# tester.net
KiCad netlist of a schematic drawn in EAGLE
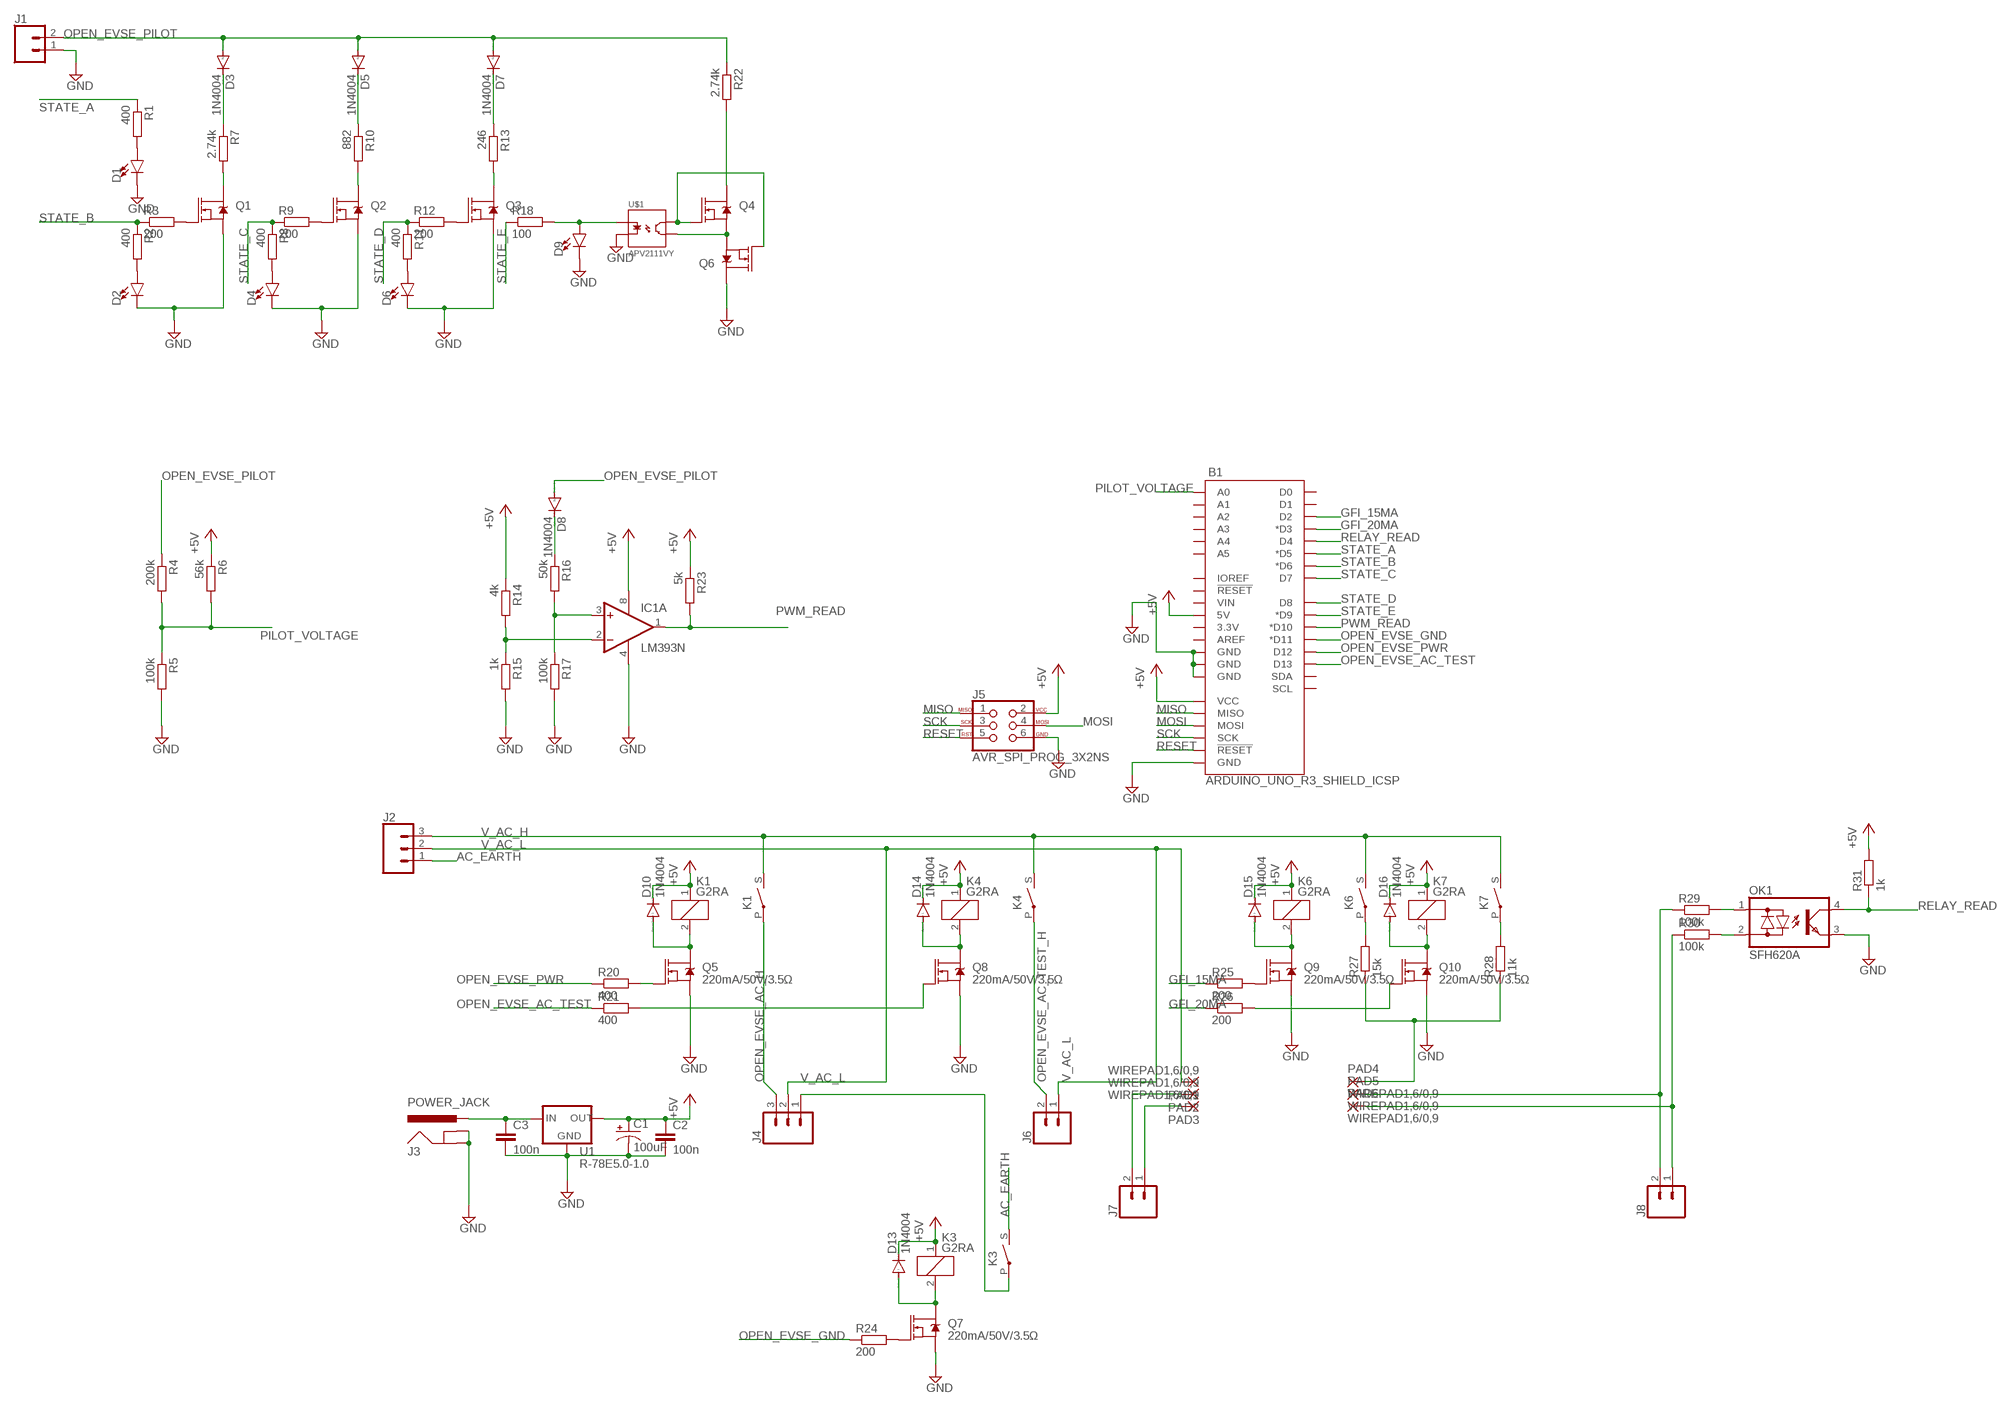
[diagram p0: schematic, sheet 1]

(export (version "E")
  (design (tool "Eeschema 10.0.6"))
  (components
    (comp (ref "B1")
      (value "ARDUINO_UNO_R3_SHIELD_ICSP")
      (footprint "eagle-import:UNO_R3_SHIELD_ICSP")
      (libsource (lib "eagle-import") (part "ARDUINO_UNO_R3_SHIELD_ICSP"))
    )
    (comp (ref "C1")
      (value "100uF")
      (footprint "eagle-import:CPOL-RADIAL-2.5MM-6.5MM")
      (libsource (lib "eagle-import") (part "100UF-POLAR-RADIAL-2.5MM-25V-20%"))
    )
    (comp (ref "C2")
      (value "100n")
      (footprint "eagle-import:C025-024X044")
      (libsource (lib "eagle-import") (part "C-EU025-024X044"))
    )
    (comp (ref "C3")
      (value "100n")
      (footprint "eagle-import:C025-024X044")
      (libsource (lib "eagle-import") (part "C-EU025-024X044"))
    )
    (comp (ref "D1")
      (value "LED-FKIT-1206")
      (footprint "eagle-import:FKIT-LED-1206")
      (libsource (lib "eagle-import") (part "LED-FKIT-1206"))
    )
    (comp (ref "D2")
      (value "LED-FKIT-1206")
      (footprint "eagle-import:FKIT-LED-1206")
      (libsource (lib "eagle-import") (part "LED-FKIT-1206"))
    )
    (comp (ref "D3")
      (value "1N4004")
      (footprint "eagle-import:DO41-10")
      (libsource (lib "eagle-import") (part "1N4004"))
    )
    (comp (ref "D4")
      (value "LED-FKIT-1206")
      (footprint "eagle-import:FKIT-LED-1206")
      (libsource (lib "eagle-import") (part "LED-FKIT-1206"))
    )
    (comp (ref "D5")
      (value "1N4004")
      (footprint "eagle-import:DO41-10")
      (libsource (lib "eagle-import") (part "1N4004"))
    )
    (comp (ref "D6")
      (value "LED-FKIT-1206")
      (footprint "eagle-import:FKIT-LED-1206")
      (libsource (lib "eagle-import") (part "LED-FKIT-1206"))
    )
    (comp (ref "D7")
      (value "1N4004")
      (footprint "eagle-import:DO41-10")
      (libsource (lib "eagle-import") (part "1N4004"))
    )
    (comp (ref "D8")
      (value "1N4004")
      (footprint "eagle-import:DO41-10")
      (libsource (lib "eagle-import") (part "1N4004"))
    )
    (comp (ref "D9")
      (value "LED-FKIT-1206")
      (footprint "eagle-import:FKIT-LED-1206")
      (libsource (lib "eagle-import") (part "LED-FKIT-1206"))
    )
    (comp (ref "D10")
      (value "1N4004")
      (footprint "eagle-import:DO41-10")
      (libsource (lib "eagle-import") (part "1N4004"))
    )
    (comp (ref "D13")
      (value "1N4004")
      (footprint "eagle-import:DO41-10")
      (libsource (lib "eagle-import") (part "1N4004"))
    )
    (comp (ref "D14")
      (value "1N4004")
      (footprint "eagle-import:DO41-10")
      (libsource (lib "eagle-import") (part "1N4004"))
    )
    (comp (ref "D15")
      (value "1N4004")
      (footprint "eagle-import:DO41-10")
      (libsource (lib "eagle-import") (part "1N4004"))
    )
    (comp (ref "D16")
      (value "1N4004")
      (footprint "eagle-import:DO41-10")
      (libsource (lib "eagle-import") (part "1N4004"))
    )
    (comp (ref "IC1")
      (value "LM393N")
      (footprint "eagle-import:DIL08")
      (libsource (lib "eagle-import") (part "LM393N"))
    )
    (comp (ref "J1")
      (value "CONN_023.5MM")
      (footprint "eagle-import:SCREWTERMINAL-3.5MM-2")
      (libsource (lib "eagle-import") (part "CONN_023.5MM"))
    )
    (comp (ref "J2")
      (value "CONN_03-SCREW-5MM")
      (footprint "eagle-import:SCREWTERMINAL-5MM-3")
      (libsource (lib "eagle-import") (part "CONN_03-SCREW-5MM"))
    )
    (comp (ref "J3")
      (value "POWER_JACK")
      (footprint "eagle-import:POWER_JACK_PTH")
      (libsource (lib "eagle-import") (part "POWER_JACK"))
    )
    (comp (ref "J4")
      (value "CONN_03-SCREW-5MM")
      (footprint "eagle-import:SCREWTERMINAL-5MM-3")
      (libsource (lib "eagle-import") (part "CONN_03-SCREW-5MM"))
    )
    (comp (ref "J5")
      (value "AVR_SPI_PROG_3X2NS")
      (footprint "eagle-import:2X3-NS")
      (libsource (lib "eagle-import") (part "AVR_SPI_PROG_3X2NS"))
    )
    (comp (ref "J6")
      (value "CONN_023.5MM")
      (footprint "eagle-import:SCREWTERMINAL-3.5MM-2")
      (libsource (lib "eagle-import") (part "CONN_023.5MM"))
    )
    (comp (ref "J7")
      (value "CONN_023.5MM")
      (footprint "eagle-import:SCREWTERMINAL-3.5MM-2")
      (libsource (lib "eagle-import") (part "CONN_023.5MM"))
    )
    (comp (ref "J8")
      (value "CONN_023.5MM")
      (footprint "eagle-import:SCREWTERMINAL-3.5MM-2")
      (libsource (lib "eagle-import") (part "CONN_023.5MM"))
    )
    (comp (ref "K1")
      (value "G2RA")
      (footprint "eagle-import:G2RA")
      (libsource (lib "eagle-import") (part "G2RA"))
    )
    (comp (ref "K3")
      (value "G2RA")
      (footprint "eagle-import:G2RA")
      (libsource (lib "eagle-import") (part "G2RA"))
    )
    (comp (ref "K4")
      (value "G2RA")
      (footprint "eagle-import:G2RA")
      (libsource (lib "eagle-import") (part "G2RA"))
    )
    (comp (ref "K6")
      (value "G2RA")
      (footprint "eagle-import:G2RA")
      (libsource (lib "eagle-import") (part "G2RA"))
    )
    (comp (ref "K7")
      (value "G2RA")
      (footprint "eagle-import:G2RA")
      (libsource (lib "eagle-import") (part "G2RA"))
    )
    (comp (ref "OK1")
      (value "SFH620A")
      (footprint "eagle-import:DIL04")
      (fields (field (name "MPN") "SFH620A-2"))
      (libsource (lib "eagle-import") (part "SFH620A"))
    )
    (comp (ref "PAD1")
      (value "WIREPAD1,6/0,9")
      (footprint "eagle-import:1,6_0,9")
      (libsource (lib "eagle-import") (part "WIREPAD1,6/0,9"))
    )
    (comp (ref "PAD2")
      (value "WIREPAD1,6/0,9")
      (footprint "eagle-import:1,6_0,9")
      (libsource (lib "eagle-import") (part "WIREPAD1,6/0,9"))
    )
    (comp (ref "PAD3")
      (value "WIREPAD1,6/0,9")
      (footprint "eagle-import:1,6_0,9")
      (libsource (lib "eagle-import") (part "WIREPAD1,6/0,9"))
    )
    (comp (ref "PAD4")
      (value "WIREPAD1,6/0,9")
      (footprint "eagle-import:1,6_0,9")
      (libsource (lib "eagle-import") (part "WIREPAD1,6/0,9"))
    )
    (comp (ref "PAD5")
      (value "WIREPAD1,6/0,9")
      (footprint "eagle-import:1,6_0,9")
      (libsource (lib "eagle-import") (part "WIREPAD1,6/0,9"))
    )
    (comp (ref "PAD6")
      (value "WIREPAD1,6/0,9")
      (footprint "eagle-import:1,6_0,9")
      (libsource (lib "eagle-import") (part "WIREPAD1,6/0,9"))
    )
    (comp (ref "Q1")
      (value "220mA/50V/3.5Ω")
      (footprint "eagle-import:SOT23-3")
      (libsource (lib "eagle-import") (part "MOSFET-NCH-BSS138"))
    )
    (comp (ref "Q2")
      (value "220mA/50V/3.5Ω")
      (footprint "eagle-import:SOT23-3")
      (libsource (lib "eagle-import") (part "MOSFET-NCH-BSS138"))
    )
    (comp (ref "Q3")
      (value "220mA/50V/3.5Ω")
      (footprint "eagle-import:SOT23-3")
      (libsource (lib "eagle-import") (part "MOSFET-NCH-BSS138"))
    )
    (comp (ref "Q4")
      (value "220mA/50V/3.5Ω")
      (footprint "eagle-import:SOT23-3")
      (libsource (lib "eagle-import") (part "MOSFET-NCH-BSS138"))
    )
    (comp (ref "Q5")
      (value "220mA/50V/3.5Ω")
      (footprint "eagle-import:SOT23-3")
      (libsource (lib "eagle-import") (part "MOSFET-NCH-BSS138"))
    )
    (comp (ref "Q6")
      (value "220mA/50V/3.5Ω")
      (footprint "eagle-import:SOT23-3")
      (libsource (lib "eagle-import") (part "MOSFET-NCH-BSS138"))
    )
    (comp (ref "Q7")
      (value "220mA/50V/3.5Ω")
      (footprint "eagle-import:SOT23-3")
      (libsource (lib "eagle-import") (part "MOSFET-NCH-BSS138"))
    )
    (comp (ref "Q8")
      (value "220mA/50V/3.5Ω")
      (footprint "eagle-import:SOT23-3")
      (libsource (lib "eagle-import") (part "MOSFET-NCH-BSS138"))
    )
    (comp (ref "Q9")
      (value "220mA/50V/3.5Ω")
      (footprint "eagle-import:SOT23-3")
      (libsource (lib "eagle-import") (part "MOSFET-NCH-BSS138"))
    )
    (comp (ref "Q10")
      (value "220mA/50V/3.5Ω")
      (footprint "eagle-import:SOT23-3")
      (libsource (lib "eagle-import") (part "MOSFET-NCH-BSS138"))
    )
    (comp (ref "R1")
      (value "400")
      (footprint "eagle-import:R1206")
      (libsource (lib "eagle-import") (part "R-EU_R1206"))
    )
    (comp (ref "R2")
      (value "400")
      (footprint "eagle-import:R1206")
      (libsource (lib "eagle-import") (part "R-EU_R1206"))
    )
    (comp (ref "R3")
      (value "200")
      (footprint "eagle-import:R1206")
      (libsource (lib "eagle-import") (part "R-EU_R1206"))
    )
    (comp (ref "R4")
      (value "200k")
      (footprint "eagle-import:R1206")
      (libsource (lib "eagle-import") (part "R-EU_R1206"))
    )
    (comp (ref "R5")
      (value "100k")
      (footprint "eagle-import:R1206")
      (libsource (lib "eagle-import") (part "R-EU_R1206"))
    )
    (comp (ref "R6")
      (value "56k")
      (footprint "eagle-import:R1206")
      (libsource (lib "eagle-import") (part "R-EU_R1206"))
    )
    (comp (ref "R7")
      (value "2.74k")
      (footprint "eagle-import:R1206")
      (libsource (lib "eagle-import") (part "R-EU_R1206"))
    )
    (comp (ref "R8")
      (value "400")
      (footprint "eagle-import:R1206")
      (libsource (lib "eagle-import") (part "R-EU_R1206"))
    )
    (comp (ref "R9")
      (value "200")
      (footprint "eagle-import:R1206")
      (libsource (lib "eagle-import") (part "R-EU_R1206"))
    )
    (comp (ref "R10")
      (value "882")
      (footprint "eagle-import:R1206")
      (libsource (lib "eagle-import") (part "R-EU_R1206"))
    )
    (comp (ref "R11")
      (value "400")
      (footprint "eagle-import:R1206")
      (libsource (lib "eagle-import") (part "R-EU_R1206"))
    )
    (comp (ref "R12")
      (value "200")
      (footprint "eagle-import:R1206")
      (libsource (lib "eagle-import") (part "R-EU_R1206"))
    )
    (comp (ref "R13")
      (value "246")
      (footprint "eagle-import:R1206")
      (libsource (lib "eagle-import") (part "R-EU_R1206"))
    )
    (comp (ref "R14")
      (value "4k")
      (footprint "eagle-import:R1206")
      (libsource (lib "eagle-import") (part "R-EU_R1206"))
    )
    (comp (ref "R15")
      (value "1k")
      (footprint "eagle-import:R1206")
      (libsource (lib "eagle-import") (part "R-EU_R1206"))
    )
    (comp (ref "R16")
      (value "50k")
      (footprint "eagle-import:R1206")
      (libsource (lib "eagle-import") (part "R-EU_R1206"))
    )
    (comp (ref "R17")
      (value "100k")
      (footprint "eagle-import:R1206")
      (libsource (lib "eagle-import") (part "R-EU_R1206"))
    )
    (comp (ref "R18")
      (value "100")
      (footprint "eagle-import:R1206")
      (libsource (lib "eagle-import") (part "R-EU_R1206"))
    )
    (comp (ref "R20")
      (value "400")
      (footprint "eagle-import:R1206")
      (libsource (lib "eagle-import") (part "R-EU_R1206"))
    )
    (comp (ref "R21")
      (value "400")
      (footprint "eagle-import:R1206")
      (libsource (lib "eagle-import") (part "R-EU_R1206"))
    )
    (comp (ref "R22")
      (value "2.74k")
      (footprint "eagle-import:R1206")
      (libsource (lib "eagle-import") (part "R-EU_R1206"))
    )
    (comp (ref "R23")
      (value "5k")
      (footprint "eagle-import:R1206")
      (libsource (lib "eagle-import") (part "R-EU_R1206"))
    )
    (comp (ref "R24")
      (value "200")
      (footprint "eagle-import:R1206")
      (libsource (lib "eagle-import") (part "R-EU_R1206"))
    )
    (comp (ref "R25")
      (value "200")
      (footprint "eagle-import:R1206")
      (libsource (lib "eagle-import") (part "R-EU_R1206"))
    )
    (comp (ref "R26")
      (value "200")
      (footprint "eagle-import:R1206")
      (libsource (lib "eagle-import") (part "R-EU_R1206"))
    )
    (comp (ref "R27")
      (value "15k")
      (footprint "eagle-import:0204_5")
      (libsource (lib "eagle-import") (part "R-EU_0204/5"))
    )
    (comp (ref "R28")
      (value "11k")
      (footprint "eagle-import:0204_5")
      (libsource (lib "eagle-import") (part "R-EU_0204/5"))
    )
    (comp (ref "R29")
      (value "100k")
      (footprint "eagle-import:0204_5")
      (libsource (lib "eagle-import") (part "R-EU_0204/5"))
    )
    (comp (ref "R30")
      (value "100k")
      (footprint "eagle-import:0204_5")
      (libsource (lib "eagle-import") (part "R-EU_0204/5"))
    )
    (comp (ref "R31")
      (value "1k")
      (footprint "eagle-import:R1206")
      (libsource (lib "eagle-import") (part "R-EU_R1206"))
    )
    (comp (ref "U$1")
      (value "APV2111VY")
      (footprint "eagle-import:SSOP4")
      (libsource (lib "eagle-import") (part "APV2111VY"))
    )
    (comp (ref "U1")
      (value "R-78E5.0-1.0")
      (footprint "eagle-import:DC-DC_CONVERTER_78XX")
      (libsource (lib "eagle-import") (part "R-78E5.0-1.0"))
    )
  )
  (nets
    (net (code "1") (name "+5V") (class "Default")
      (node (ref "B1") (pin "5V") (pinfunction "5V_5V") (pintype "bidirectional"))
      (node (ref "B1") (pin "5V_ICSP") (pinfunction "VCC_5V_ICSP") (pintype "bidirectional"))
      (node (ref "C1") (pin "1") (pinfunction "+_1") (pintype "passive"))
      (node (ref "C2") (pin "1") (pinfunction "1_1") (pintype "passive"))
      (node (ref "D10") (pin "C") (pinfunction "C_C") (pintype "passive"))
      (node (ref "D13") (pin "C") (pinfunction "C_C") (pintype "passive"))
      (node (ref "D14") (pin "C") (pinfunction "C_C") (pintype "passive"))
      (node (ref "D15") (pin "C") (pinfunction "C_C") (pintype "passive"))
      (node (ref "D16") (pin "C") (pinfunction "C_C") (pintype "passive"))
      (node (ref "IC1") (pin "8") (pinfunction "V+_8") (pintype "power_in"))
      (node (ref "J5") (pin "2") (pinfunction "2_2") (pintype "passive"))
      (node (ref "K1") (pin "1") (pinfunction "1_1") (pintype "passive"))
      (node (ref "K3") (pin "1") (pinfunction "1_1") (pintype "passive"))
      (node (ref "K4") (pin "1") (pinfunction "1_1") (pintype "passive"))
      (node (ref "K6") (pin "1") (pinfunction "1_1") (pintype "passive"))
      (node (ref "K7") (pin "1") (pinfunction "1_1") (pintype "passive"))
      (node (ref "R14") (pin "1") (pinfunction "1_1") (pintype "passive"))
      (node (ref "R23") (pin "1") (pinfunction "1_1") (pintype "passive"))
      (node (ref "R31") (pin "2") (pinfunction "2_2") (pintype "passive"))
      (node (ref "R6") (pin "1") (pinfunction "1_1") (pintype "passive"))
      (node (ref "U1") (pin "VOUT") (pinfunction "OUT_VOUT") (pintype "passive"))
    )
    (net (code "2") (name "/AC_EARTH") (class "Default")
      (node (ref "J2") (pin "1") (pinfunction "1_1") (pintype "passive"))
      (node (ref "K3") (pin "S") (pinfunction "S_S") (pintype "passive"))
    )
    (net (code "3") (name "/GFI_15MA") (class "Default")
      (node (ref "B1") (pin "D2") (pinfunction "D2_D2") (pintype "bidirectional"))
      (node (ref "R25") (pin "1") (pinfunction "1_1") (pintype "passive"))
    )
    (net (code "4") (name "/GFI_20MA") (class "Default")
      (node (ref "B1") (pin "D3") (pinfunction "*D3_D3") (pintype "bidirectional"))
      (node (ref "R26") (pin "1") (pinfunction "1_1") (pintype "passive"))
    )
    (net (code "5") (name "/MISO") (class "Default")
      (node (ref "B1") (pin "MISO") (pinfunction "MISO_MISO") (pintype "bidirectional"))
      (node (ref "J5") (pin "1") (pinfunction "1_1") (pintype "passive"))
    )
    (net (code "6") (name "/MOSI") (class "Default")
      (node (ref "B1") (pin "MOSI") (pinfunction "MOSI_MOSI") (pintype "bidirectional"))
      (node (ref "J5") (pin "4") (pinfunction "4_4") (pintype "passive"))
    )
    (net (code "7") (name "/OPEN_EVSE_AC_H") (class "Default")
      (node (ref "J4") (pin "3") (pinfunction "3_3") (pintype "passive"))
      (node (ref "K1") (pin "P") (pinfunction "P_P") (pintype "passive"))
    )
    (net (code "8") (name "/OPEN_EVSE_AC_TEST") (class "Default")
      (node (ref "B1") (pin "D13") (pinfunction "D13_D13") (pintype "bidirectional"))
      (node (ref "R21") (pin "1") (pinfunction "1_1") (pintype "passive"))
    )
    (net (code "9") (name "/OPEN_EVSE_AC_TEST_H") (class "Default")
      (node (ref "J6") (pin "2") (pinfunction "2_2") (pintype "passive"))
      (node (ref "K4") (pin "P") (pinfunction "P_P") (pintype "passive"))
    )
    (net (code "10") (name "/OPEN_EVSE_GND") (class "Default")
      (node (ref "B1") (pin "D11") (pinfunction "*D11_D11") (pintype "bidirectional"))
      (node (ref "R24") (pin "1") (pinfunction "1_1") (pintype "passive"))
    )
    (net (code "11") (name "/OPEN_EVSE_PILOT") (class "Default")
      (node (ref "D3") (pin "A") (pinfunction "A_A") (pintype "passive"))
      (node (ref "D5") (pin "A") (pinfunction "A_A") (pintype "passive"))
      (node (ref "D7") (pin "A") (pinfunction "A_A") (pintype "passive"))
      (node (ref "D8") (pin "A") (pinfunction "A_A") (pintype "passive"))
      (node (ref "J1") (pin "2") (pinfunction "2_2") (pintype "passive"))
      (node (ref "R22") (pin "1") (pinfunction "1_1") (pintype "passive"))
      (node (ref "R4") (pin "1") (pinfunction "1_1") (pintype "passive"))
    )
    (net (code "12") (name "/OPEN_EVSE_PWR") (class "Default")
      (node (ref "B1") (pin "D12") (pinfunction "D12_D12") (pintype "bidirectional"))
      (node (ref "R20") (pin "1") (pinfunction "1_1") (pintype "passive"))
    )
    (net (code "13") (name "/PILOT_VOLTAGE") (class "Default")
      (node (ref "B1") (pin "A0") (pinfunction "A0_A0") (pintype "bidirectional"))
      (node (ref "R4") (pin "2") (pinfunction "2_2") (pintype "passive"))
      (node (ref "R5") (pin "1") (pinfunction "1_1") (pintype "passive"))
      (node (ref "R6") (pin "2") (pinfunction "2_2") (pintype "passive"))
    )
    (net (code "14") (name "/PWM_READ") (class "Default")
      (node (ref "B1") (pin "D10") (pinfunction "*D10_D10") (pintype "bidirectional"))
      (node (ref "IC1") (pin "1") (pinfunction "OUT_1") (pintype "output"))
      (node (ref "R23") (pin "2") (pinfunction "2_2") (pintype "passive"))
    )
    (net (code "15") (name "/RELAY_READ") (class "Default")
      (node (ref "B1") (pin "D4") (pinfunction "D4_D4") (pintype "bidirectional"))
      (node (ref "OK1") (pin "4") (pinfunction "C_4") (pintype "passive"))
      (node (ref "R31") (pin "1") (pinfunction "1_1") (pintype "passive"))
    )
    (net (code "16") (name "/RESET") (class "Default")
      (node (ref "B1") (pin "RST_ICSP") (pinfunction "~{RESET}_RST_ICSP") (pintype "bidirectional"))
      (node (ref "J5") (pin "5") (pinfunction "5_5") (pintype "passive"))
    )
    (net (code "17") (name "/SCK") (class "Default")
      (node (ref "B1") (pin "SCK") (pinfunction "SCK_SCK") (pintype "bidirectional"))
      (node (ref "J5") (pin "3") (pinfunction "3_3") (pintype "passive"))
    )
    (net (code "18") (name "/STATE_A") (class "Default")
      (node (ref "B1") (pin "D5") (pinfunction "*D5_D5") (pintype "bidirectional"))
      (node (ref "R1") (pin "1") (pinfunction "1_1") (pintype "passive"))
    )
    (net (code "19") (name "/STATE_B") (class "Default")
      (node (ref "B1") (pin "D6") (pinfunction "*D6_D6") (pintype "bidirectional"))
      (node (ref "R2") (pin "1") (pinfunction "1_1") (pintype "passive"))
      (node (ref "R3") (pin "1") (pinfunction "1_1") (pintype "passive"))
    )
    (net (code "20") (name "/STATE_C") (class "Default")
      (node (ref "B1") (pin "D7") (pinfunction "D7_D7") (pintype "bidirectional"))
      (node (ref "R8") (pin "1") (pinfunction "1_1") (pintype "passive"))
      (node (ref "R9") (pin "1") (pinfunction "1_1") (pintype "passive"))
    )
    (net (code "21") (name "/STATE_D") (class "Default")
      (node (ref "B1") (pin "D8") (pinfunction "D8_D8") (pintype "bidirectional"))
      (node (ref "R11") (pin "1") (pinfunction "1_1") (pintype "passive"))
      (node (ref "R12") (pin "1") (pinfunction "1_1") (pintype "passive"))
    )
    (net (code "22") (name "/STATE_E") (class "Default")
      (node (ref "B1") (pin "D9") (pinfunction "*D9_D9") (pintype "bidirectional"))
      (node (ref "R18") (pin "1") (pinfunction "1_1") (pintype "passive"))
    )
    (net (code "23") (name "/V_AC_H") (class "Default")
      (node (ref "J2") (pin "3") (pinfunction "3_3") (pintype "passive"))
      (node (ref "K1") (pin "S") (pinfunction "S_S") (pintype "passive"))
      (node (ref "K4") (pin "S") (pinfunction "S_S") (pintype "passive"))
      (node (ref "K6") (pin "S") (pinfunction "S_S") (pintype "passive"))
      (node (ref "K7") (pin "S") (pinfunction "S_S") (pintype "passive"))
    )
    (net (code "24") (name "/V_AC_L") (class "Default")
      (node (ref "J2") (pin "2") (pinfunction "2_2") (pintype "passive"))
      (node (ref "J4") (pin "2") (pinfunction "2_2") (pintype "passive"))
      (node (ref "J6") (pin "1") (pinfunction "1_1") (pintype "passive"))
      (node (ref "PAD1") (pin "1") (pinfunction "P_1") (pintype "passive"))
    )
    (net (code "25") (name "GND") (class "Default")
      (node (ref "B1") (pin "GND@0") (pinfunction "GND_GND@0") (pintype "bidirectional"))
      (node (ref "B1") (pin "GND@1") (pinfunction "GND_GND@1") (pintype "bidirectional"))
      (node (ref "B1") (pin "GND@2") (pinfunction "GND_GND@2") (pintype "bidirectional"))
      (node (ref "B1") (pin "GND_ICSP") (pinfunction "GND_GND_ICSP") (pintype "bidirectional"))
      (node (ref "C1") (pin "2") (pinfunction "-_2") (pintype "passive"))
      (node (ref "C2") (pin "2") (pinfunction "2_2") (pintype "passive"))
      (node (ref "C3") (pin "2") (pinfunction "2_2") (pintype "passive"))
      (node (ref "D1") (pin "C") (pinfunction "C_C") (pintype "passive"))
      (node (ref "D2") (pin "C") (pinfunction "C_C") (pintype "passive"))
      (node (ref "D4") (pin "C") (pinfunction "C_C") (pintype "passive"))
      (node (ref "D6") (pin "C") (pinfunction "C_C") (pintype "passive"))
      (node (ref "D9") (pin "C") (pinfunction "C_C") (pintype "passive"))
      (node (ref "IC1") (pin "4") (pinfunction "V-_4") (pintype "power_in"))
      (node (ref "J1") (pin "1") (pinfunction "1_1") (pintype "passive"))
      (node (ref "J3") (pin "GND") (pinfunction "GND_GND") (pintype "bidirectional"))
      (node (ref "J3") (pin "GNDBREAK") (pinfunction "GNDBREAK_GNDBREAK") (pintype "bidirectional"))
      (node (ref "J5") (pin "6") (pinfunction "6_6") (pintype "passive"))
      (node (ref "OK1") (pin "3") (pinfunction "E_3") (pintype "passive"))
      (node (ref "Q1") (pin "2") (pinfunction "S_2") (pintype "bidirectional"))
      (node (ref "Q10") (pin "2") (pinfunction "S_2") (pintype "bidirectional"))
      (node (ref "Q2") (pin "2") (pinfunction "S_2") (pintype "bidirectional"))
      (node (ref "Q3") (pin "2") (pinfunction "S_2") (pintype "bidirectional"))
      (node (ref "Q5") (pin "2") (pinfunction "S_2") (pintype "bidirectional"))
      (node (ref "Q6") (pin "3") (pinfunction "D_3") (pintype "bidirectional"))
      (node (ref "Q7") (pin "2") (pinfunction "S_2") (pintype "bidirectional"))
      (node (ref "Q8") (pin "2") (pinfunction "S_2") (pintype "bidirectional"))
      (node (ref "Q9") (pin "2") (pinfunction "S_2") (pintype "bidirectional"))
      (node (ref "R15") (pin "2") (pinfunction "2_2") (pintype "passive"))
      (node (ref "R17") (pin "2") (pinfunction "2_2") (pintype "passive"))
      (node (ref "R5") (pin "2") (pinfunction "2_2") (pintype "passive"))
      (node (ref "U$1") (pin "2") (pinfunction "C1_2") (pintype "bidirectional"))
      (node (ref "U1") (pin "GND") (pinfunction "GND_GND") (pintype "input"))
    )
    (net (code "26") (name "Net-(D1-PadA)") (class "Default")
      (node (ref "D1") (pin "A") (pinfunction "A_A") (pintype "passive"))
      (node (ref "R1") (pin "2") (pinfunction "2_2") (pintype "passive"))
    )
    (net (code "27") (name "Net-(D2-PadA)") (class "Default")
      (node (ref "D2") (pin "A") (pinfunction "A_A") (pintype "passive"))
      (node (ref "R2") (pin "2") (pinfunction "2_2") (pintype "passive"))
    )
    (net (code "28") (name "Net-(D3-PadC)") (class "Default")
      (node (ref "D3") (pin "C") (pinfunction "C_C") (pintype "passive"))
      (node (ref "R7") (pin "1") (pinfunction "1_1") (pintype "passive"))
    )
    (net (code "29") (name "Net-(D4-PadA)") (class "Default")
      (node (ref "D4") (pin "A") (pinfunction "A_A") (pintype "passive"))
      (node (ref "R8") (pin "2") (pinfunction "2_2") (pintype "passive"))
    )
    (net (code "30") (name "Net-(D5-PadC)") (class "Default")
      (node (ref "D5") (pin "C") (pinfunction "C_C") (pintype "passive"))
      (node (ref "R10") (pin "1") (pinfunction "1_1") (pintype "passive"))
    )
    (net (code "31") (name "Net-(D6-PadA)") (class "Default")
      (node (ref "D6") (pin "A") (pinfunction "A_A") (pintype "passive"))
      (node (ref "R11") (pin "2") (pinfunction "2_2") (pintype "passive"))
    )
    (net (code "32") (name "Net-(D7-PadC)") (class "Default")
      (node (ref "D7") (pin "C") (pinfunction "C_C") (pintype "passive"))
      (node (ref "R13") (pin "1") (pinfunction "1_1") (pintype "passive"))
    )
    (net (code "33") (name "Net-(D8-PadC)") (class "Default")
      (node (ref "D8") (pin "C") (pinfunction "C_C") (pintype "passive"))
      (node (ref "R16") (pin "1") (pinfunction "1_1") (pintype "passive"))
    )
    (net (code "34") (name "Net-(IC1A-+IN)") (class "Default")
      (node (ref "IC1") (pin "3") (pinfunction "+IN_3") (pintype "input"))
      (node (ref "R16") (pin "2") (pinfunction "2_2") (pintype "passive"))
      (node (ref "R17") (pin "1") (pinfunction "1_1") (pintype "passive"))
    )
    (net (code "35") (name "Net-(IC1A--IN)") (class "Default")
      (node (ref "IC1") (pin "2") (pinfunction "-IN_2") (pintype "input"))
      (node (ref "R14") (pin "2") (pinfunction "2_2") (pintype "passive"))
      (node (ref "R15") (pin "1") (pinfunction "1_1") (pintype "passive"))
    )
    (net (code "36") (name "Net-(J4-Pad1)") (class "Default")
      (node (ref "J4") (pin "1") (pinfunction "1_1") (pintype "passive"))
      (node (ref "K3") (pin "P") (pinfunction "P_P") (pintype "passive"))
    )
    (net (code "37") (name "Net-(K6-PadP)") (class "Default")
      (node (ref "K6") (pin "P") (pinfunction "P_P") (pintype "passive"))
      (node (ref "R27") (pin "2") (pinfunction "2_2") (pintype "passive"))
    )
    (net (code "38") (name "Net-(K7-PadP)") (class "Default")
      (node (ref "K7") (pin "P") (pinfunction "P_P") (pintype "passive"))
      (node (ref "R28") (pin "2") (pinfunction "2_2") (pintype "passive"))
    )
    (net (code "39") (name "Net-(OK1-AC1)") (class "Default")
      (node (ref "OK1") (pin "1") (pinfunction "AC1_1") (pintype "passive"))
      (node (ref "R29") (pin "2") (pinfunction "2_2") (pintype "passive"))
    )
    (net (code "40") (name "Net-(OK1-AC2)") (class "Default")
      (node (ref "OK1") (pin "2") (pinfunction "AC2_2") (pintype "passive"))
      (node (ref "R30") (pin "2") (pinfunction "2_2") (pintype "passive"))
    )
    (net (code "41") (name "Net-(PAD2-P)") (class "Default")
      (node (ref "J7") (pin "2") (pinfunction "2_2") (pintype "passive"))
      (node (ref "PAD2") (pin "1") (pinfunction "P_1") (pintype "passive"))
    )
    (net (code "42") (name "Net-(PAD3-P)") (class "Default")
      (node (ref "J7") (pin "1") (pinfunction "1_1") (pintype "passive"))
      (node (ref "PAD3") (pin "1") (pinfunction "P_1") (pintype "passive"))
    )
    (net (code "43") (name "Net-(PAD4-P)") (class "Default")
      (node (ref "PAD4") (pin "1") (pinfunction "P_1") (pintype "passive"))
      (node (ref "R27") (pin "1") (pinfunction "1_1") (pintype "passive"))
      (node (ref "R28") (pin "1") (pinfunction "1_1") (pintype "passive"))
    )
    (net (code "44") (name "Net-(PAD5-P)") (class "Default")
      (node (ref "J8") (pin "2") (pinfunction "2_2") (pintype "passive"))
      (node (ref "PAD5") (pin "1") (pinfunction "P_1") (pintype "passive"))
      (node (ref "R29") (pin "1") (pinfunction "1_1") (pintype "passive"))
    )
    (net (code "45") (name "Net-(PAD6-P)") (class "Default")
      (node (ref "J8") (pin "1") (pinfunction "1_1") (pintype "passive"))
      (node (ref "PAD6") (pin "1") (pinfunction "P_1") (pintype "passive"))
      (node (ref "R30") (pin "1") (pinfunction "1_1") (pintype "passive"))
    )
    (net (code "46") (name "Net-(Q1-D)") (class "Default")
      (node (ref "Q1") (pin "3") (pinfunction "D_3") (pintype "bidirectional"))
      (node (ref "R7") (pin "2") (pinfunction "2_2") (pintype "passive"))
    )
    (net (code "47") (name "Net-(Q1-G)") (class "Default")
      (node (ref "Q1") (pin "1") (pinfunction "G_1") (pintype "bidirectional"))
      (node (ref "R3") (pin "2") (pinfunction "2_2") (pintype "passive"))
    )
    (net (code "48") (name "Net-(Q2-D)") (class "Default")
      (node (ref "Q2") (pin "3") (pinfunction "D_3") (pintype "bidirectional"))
      (node (ref "R10") (pin "2") (pinfunction "2_2") (pintype "passive"))
    )
    (net (code "49") (name "Net-(Q2-G)") (class "Default")
      (node (ref "Q2") (pin "1") (pinfunction "G_1") (pintype "bidirectional"))
      (node (ref "R9") (pin "2") (pinfunction "2_2") (pintype "passive"))
    )
    (net (code "50") (name "Net-(Q3-D)") (class "Default")
      (node (ref "Q3") (pin "3") (pinfunction "D_3") (pintype "bidirectional"))
      (node (ref "R13") (pin "2") (pinfunction "2_2") (pintype "passive"))
    )
    (net (code "51") (name "Net-(Q3-G)") (class "Default")
      (node (ref "Q3") (pin "1") (pinfunction "G_1") (pintype "bidirectional"))
      (node (ref "R12") (pin "2") (pinfunction "2_2") (pintype "passive"))
    )
    (net (code "52") (name "Net-(Q4-D)") (class "Default")
      (node (ref "Q4") (pin "3") (pinfunction "D_3") (pintype "bidirectional"))
      (node (ref "R22") (pin "2") (pinfunction "2_2") (pintype "passive"))
    )
    (net (code "53") (name "Net-(Q4-G)") (class "Default")
      (node (ref "Q4") (pin "1") (pinfunction "G_1") (pintype "bidirectional"))
      (node (ref "Q6") (pin "1") (pinfunction "G_1") (pintype "bidirectional"))
      (node (ref "U$1") (pin "3") (pinfunction "CL1_3") (pintype "bidirectional"))
    )
    (net (code "54") (name "Net-(Q4-S)") (class "Default")
      (node (ref "Q4") (pin "2") (pinfunction "S_2") (pintype "bidirectional"))
      (node (ref "Q6") (pin "2") (pinfunction "S_2") (pintype "bidirectional"))
      (node (ref "U$1") (pin "4") (pinfunction "EM1_4") (pintype "bidirectional"))
    )
    (net (code "55") (name "Net-(Q5-D)") (class "Default")
      (node (ref "D10") (pin "A") (pinfunction "A_A") (pintype "passive"))
      (node (ref "K1") (pin "2") (pinfunction "2_2") (pintype "passive"))
      (node (ref "Q5") (pin "3") (pinfunction "D_3") (pintype "bidirectional"))
    )
    (net (code "56") (name "Net-(Q5-G)") (class "Default")
      (node (ref "Q5") (pin "1") (pinfunction "G_1") (pintype "bidirectional"))
      (node (ref "R20") (pin "2") (pinfunction "2_2") (pintype "passive"))
    )
    (net (code "57") (name "Net-(Q7-D)") (class "Default")
      (node (ref "D13") (pin "A") (pinfunction "A_A") (pintype "passive"))
      (node (ref "K3") (pin "2") (pinfunction "2_2") (pintype "passive"))
      (node (ref "Q7") (pin "3") (pinfunction "D_3") (pintype "bidirectional"))
    )
    (net (code "58") (name "Net-(Q7-G)") (class "Default")
      (node (ref "Q7") (pin "1") (pinfunction "G_1") (pintype "bidirectional"))
      (node (ref "R24") (pin "2") (pinfunction "2_2") (pintype "passive"))
    )
    (net (code "59") (name "Net-(Q8-D)") (class "Default")
      (node (ref "D14") (pin "A") (pinfunction "A_A") (pintype "passive"))
      (node (ref "K4") (pin "2") (pinfunction "2_2") (pintype "passive"))
      (node (ref "Q8") (pin "3") (pinfunction "D_3") (pintype "bidirectional"))
    )
    (net (code "60") (name "Net-(Q8-G)") (class "Default")
      (node (ref "Q8") (pin "1") (pinfunction "G_1") (pintype "bidirectional"))
      (node (ref "R21") (pin "2") (pinfunction "2_2") (pintype "passive"))
    )
    (net (code "61") (name "Net-(Q9-D)") (class "Default")
      (node (ref "D15") (pin "A") (pinfunction "A_A") (pintype "passive"))
      (node (ref "K6") (pin "2") (pinfunction "2_2") (pintype "passive"))
      (node (ref "Q9") (pin "3") (pinfunction "D_3") (pintype "bidirectional"))
    )
    (net (code "62") (name "Net-(Q9-G)") (class "Default")
      (node (ref "Q9") (pin "1") (pinfunction "G_1") (pintype "bidirectional"))
      (node (ref "R25") (pin "2") (pinfunction "2_2") (pintype "passive"))
    )
    (net (code "63") (name "Net-(Q10-D)") (class "Default")
      (node (ref "D16") (pin "A") (pinfunction "A_A") (pintype "passive"))
      (node (ref "K7") (pin "2") (pinfunction "2_2") (pintype "passive"))
      (node (ref "Q10") (pin "3") (pinfunction "D_3") (pintype "bidirectional"))
    )
    (net (code "64") (name "Net-(Q10-G)") (class "Default")
      (node (ref "Q10") (pin "1") (pinfunction "G_1") (pintype "bidirectional"))
      (node (ref "R26") (pin "2") (pinfunction "2_2") (pintype "passive"))
    )
    (net (code "65") (name "Net-(U$1-A1)") (class "Default")
      (node (ref "D9") (pin "A") (pinfunction "A_A") (pintype "passive"))
      (node (ref "R18") (pin "2") (pinfunction "2_2") (pintype "passive"))
      (node (ref "U$1") (pin "1") (pinfunction "A1_1") (pintype "bidirectional"))
    )
    (net (code "66") (name "Net-(U1-IN)") (class "Default")
      (node (ref "C3") (pin "1") (pinfunction "1_1") (pintype "passive"))
      (node (ref "J3") (pin "PWR") (pinfunction "PWR_PWR") (pintype "bidirectional"))
      (node (ref "U1") (pin "VIN") (pinfunction "IN_VIN") (pintype "input"))
    )
    (net (code "67") (name "unconnected-(B1-D0-PadRX)") (class "Default")
      (node (ref "B1") (pin "RX") (pinfunction "D0_RX") (pintype "bidirectional"))
    )
    (net (code "68") (name "unconnected-(B1-D1-PadTX)") (class "Default")
      (node (ref "B1") (pin "TX") (pinfunction "D1_TX") (pintype "bidirectional"))
    )
    (net (code "69") (name "unconnected-(B1-Pad3.3V)") (class "Default")
      (node (ref "B1") (pin "3.3V") (pinfunction "3.3V_3.3V") (pintype "bidirectional"))
    )
    (net (code "70") (name "unconnected-(B1-PadA1)") (class "Default")
      (node (ref "B1") (pin "A1") (pinfunction "A1_A1") (pintype "bidirectional"))
    )
    (net (code "71") (name "unconnected-(B1-PadA2)") (class "Default")
      (node (ref "B1") (pin "A2") (pinfunction "A2_A2") (pintype "bidirectional"))
    )
    (net (code "72") (name "unconnected-(B1-PadA3)") (class "Default")
      (node (ref "B1") (pin "A3") (pinfunction "A3_A3") (pintype "bidirectional"))
    )
    (net (code "73") (name "unconnected-(B1-PadA4)") (class "Default")
      (node (ref "B1") (pin "A4") (pinfunction "A4_A4") (pintype "bidirectional"))
    )
    (net (code "74") (name "unconnected-(B1-PadA5)") (class "Default")
      (node (ref "B1") (pin "A5") (pinfunction "A5_A5") (pintype "bidirectional"))
    )
    (net (code "75") (name "unconnected-(B1-PadAREF)") (class "Default")
      (node (ref "B1") (pin "AREF") (pinfunction "AREF_AREF") (pintype "bidirectional"))
    )
    (net (code "76") (name "unconnected-(B1-PadIOREF)") (class "Default")
      (node (ref "B1") (pin "IOREF") (pinfunction "IOREF_IOREF") (pintype "bidirectional"))
    )
    (net (code "77") (name "unconnected-(B1-PadSCL)") (class "Default")
      (node (ref "B1") (pin "SCL") (pinfunction "SCL_SCL") (pintype "bidirectional"))
    )
    (net (code "78") (name "unconnected-(B1-PadSDA)") (class "Default")
      (node (ref "B1") (pin "SDA") (pinfunction "SDA_SDA") (pintype "bidirectional"))
    )
    (net (code "79") (name "unconnected-(B1-PadVIN)") (class "Default")
      (node (ref "B1") (pin "VIN") (pinfunction "VIN_VIN") (pintype "bidirectional"))
    )
    (net (code "80") (name "unconnected-(B1-~{RESET}-PadRES)") (class "Default")
      (node (ref "B1") (pin "RES") (pinfunction "~{RESET}_RES") (pintype "bidirectional"))
    )
  )
)
